# USB.net
KiCad netlist of a schematic drawn in Altium Designer
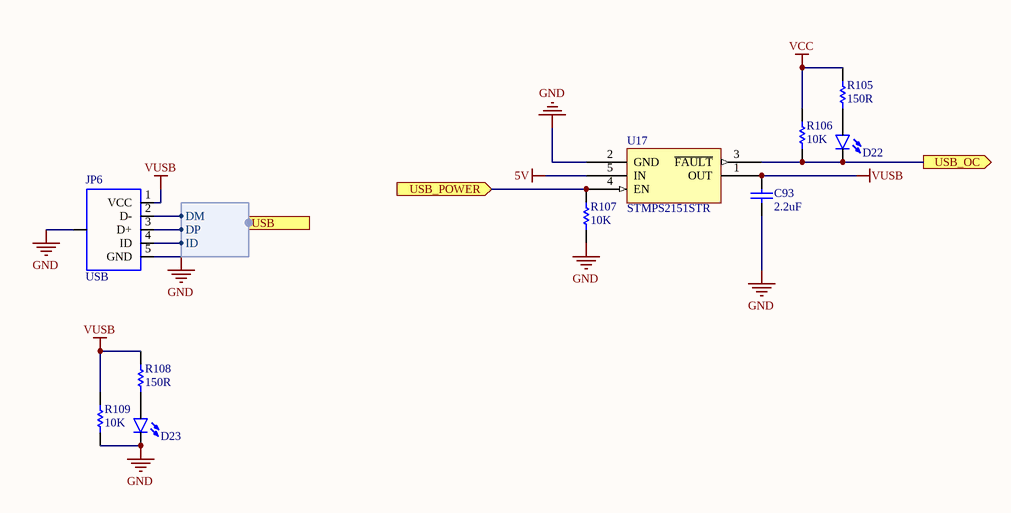
[diagram p0: USB.SchDoc]

(export (version "E")
  (design (tool "Eeschema 10.0.6"))
  (components
    (comp (ref "C93")
      (value "2.2uF")
      (footprint "C1206[3216X160]")
      (description "2.2uF 16V 10% X7R 1206 (3216 Metric)")
      (fields (field (name "PARTNUMBER") "C1206C225K4RACAUTO") (field (name "MANUFACTURER") "KEMET"))
      (libsource (lib "Capacitors") (part "CAP_2.2uF_16V_1206_10%"))
    )
    (comp (ref "D22")
      (value "USB_OC")
      (footprint "LED0603")
      (fields (field (name "PARTNUMBER") "LTST-C193TGKT-5A") (field (name "MANUFACTURER") "Lite-On Inc."))
      (libsource (lib "LEDs") (part "LED_0603_GREEN_5mA"))
    )
    (comp (ref "D23")
      (value "USB_PW")
      (footprint "LED0603")
      (fields (field (name "PARTNUMBER") "LTST-C193TGKT-5A") (field (name "MANUFACTURER") "Lite-On Inc."))
      (libsource (lib "LEDs") (part "LED_0603_GREEN_5mA"))
    )
    (comp (ref "JP6")
      (value "USB")
      (footprint "USB_MICROB_VERT")
      (fields (field (name "PARTNUMBER") "614105150721") (field (name "MANUFACTURER") "Wurth Electronics"))
      (libsource (lib "Connectors") (part "USB_MICROB_VERT"))
    )
    (comp (ref "R105")
      (value "150R")
      (footprint "R0603[1608]")
      (description "150R 0.25W 1% 0603 (1005 Metric)")
      (fields (field (name "MANUFACTURER") "Vishay / Dale") (field (name "PARTNUMBER") "CRCW0603150RFKEAHP"))
      (libsource (lib "Resistors") (part "RES_150R_0603_1%"))
    )
    (comp (ref "R106")
      (value "10K")
      (footprint "R0603[1608]")
      (description "10K 0.25W 1% 0603 (1005 Metric)")
      (fields (field (name "MANUFACTURER") "Vishay / Dale") (field (name "PARTNUMBER") "CRCW060310K0FKEAHP"))
      (libsource (lib "Resistors") (part "RES_10K_0603_1%"))
    )
    (comp (ref "R107")
      (value "10K")
      (footprint "R0603[1608]")
      (description "10K 0.25W 1% 0603 (1005 Metric)")
      (fields (field (name "MANUFACTURER") "Vishay / Dale") (field (name "PARTNUMBER") "CRCW060310K0FKEAHP"))
      (libsource (lib "Resistors") (part "RES_10K_0603_1%"))
    )
    (comp (ref "R108")
      (value "150R")
      (footprint "R0603[1608]")
      (description "150R 0.25W 1% 0603 (1005 Metric)")
      (fields (field (name "MANUFACTURER") "Vishay / Dale") (field (name "PARTNUMBER") "CRCW0603150RFKEAHP"))
      (libsource (lib "Resistors") (part "RES_150R_0603_1%"))
    )
    (comp (ref "R109")
      (value "10K")
      (footprint "R0603[1608]")
      (description "10K 0.25W 1% 0603 (1005 Metric)")
      (fields (field (name "MANUFACTURER") "Vishay / Dale") (field (name "PARTNUMBER") "CRCW060310K0FKEAHP"))
      (libsource (lib "Resistors") (part "RES_10K_0603_1%"))
    )
    (comp (ref "U17")
      (value "STMPS2151STR")
      (footprint "SOT-23-5L")
      (libsource (lib "ICs") (part "STMPS2141STR"))
    )
  )
  (nets
    (net (code "2") (name "/DM") (class "Default")
      (node (ref "JP6") (pin "2") (pinfunction "D-_2") (pintype "passive"))
    )
    (net (code "3") (name "/DP") (class "Default")
      (node (ref "JP6") (pin "3") (pinfunction "D+_3") (pintype "passive"))
    )
    (net (code "4") (name "/ID") (class "Default")
      (node (ref "JP6") (pin "4") (pinfunction "ID_4") (pintype "passive"))
    )
    (net (code "5") (name "/USB_OC") (class "Default")
      (node (ref "D22") (pin "C") (pinfunction "C_C") (pintype "passive"))
      (node (ref "R106") (pin "1") (pinfunction "1_1") (pintype "passive"))
      (node (ref "U17") (pin "3") (pinfunction "~{FAULT}_3") (pintype "output"))
    )
    (net (code "6") (name "/USB_POWER") (class "Default")
      (node (ref "R107") (pin "2") (pinfunction "2_2") (pintype "passive"))
      (node (ref "U17") (pin "4") (pinfunction "EN_4") (pintype "input"))
    )
    (net (code "8") (name "5V") (class "Default")
      (node (ref "U17") (pin "5") (pinfunction "IN_5") (pintype "passive"))
    )
    (net (code "9") (name "GND") (class "Default")
      (node (ref "C93") (pin "2") (pinfunction "2_2") (pintype "passive"))
      (node (ref "D23") (pin "C") (pinfunction "C_C") (pintype "passive"))
      (node (ref "JP6") (pin "5") (pinfunction "GND_5") (pintype "passive"))
      (node (ref "JP6") (pin "6") (pinfunction "SHIELD_6") (pintype "passive"))
      (node (ref "R107") (pin "1") (pinfunction "1_1") (pintype "passive"))
      (node (ref "R109") (pin "1") (pinfunction "1_1") (pintype "passive"))
      (node (ref "U17") (pin "2") (pinfunction "GND_2") (pintype "passive"))
    )
    (net (code "10") (name "Net-(D22-PadA)") (class "Default")
      (node (ref "D22") (pin "A") (pinfunction "A_A") (pintype "passive"))
      (node (ref "R105") (pin "1") (pinfunction "1_1") (pintype "passive"))
    )
    (net (code "11") (name "Net-(D23-PadA)") (class "Default")
      (node (ref "D23") (pin "A") (pinfunction "A_A") (pintype "passive"))
      (node (ref "R108") (pin "1") (pinfunction "1_1") (pintype "passive"))
    )
    (net (code "12") (name "VCC") (class "Default")
      (node (ref "R105") (pin "2") (pinfunction "2_2") (pintype "passive"))
      (node (ref "R106") (pin "2") (pinfunction "2_2") (pintype "passive"))
    )
    (net (code "13") (name "VUSB") (class "Default")
      (node (ref "C93") (pin "1") (pinfunction "1_1") (pintype "passive"))
      (node (ref "JP6") (pin "1") (pinfunction "VCC_1") (pintype "passive"))
      (node (ref "R108") (pin "2") (pinfunction "2_2") (pintype "passive"))
      (node (ref "R109") (pin "2") (pinfunction "2_2") (pintype "passive"))
      (node (ref "U17") (pin "1") (pinfunction "OUT_1") (pintype "passive"))
    )
  )
)
